# HANC_Analog_TS.net
KiCad netlist of a schematic drawn in Altium Designer
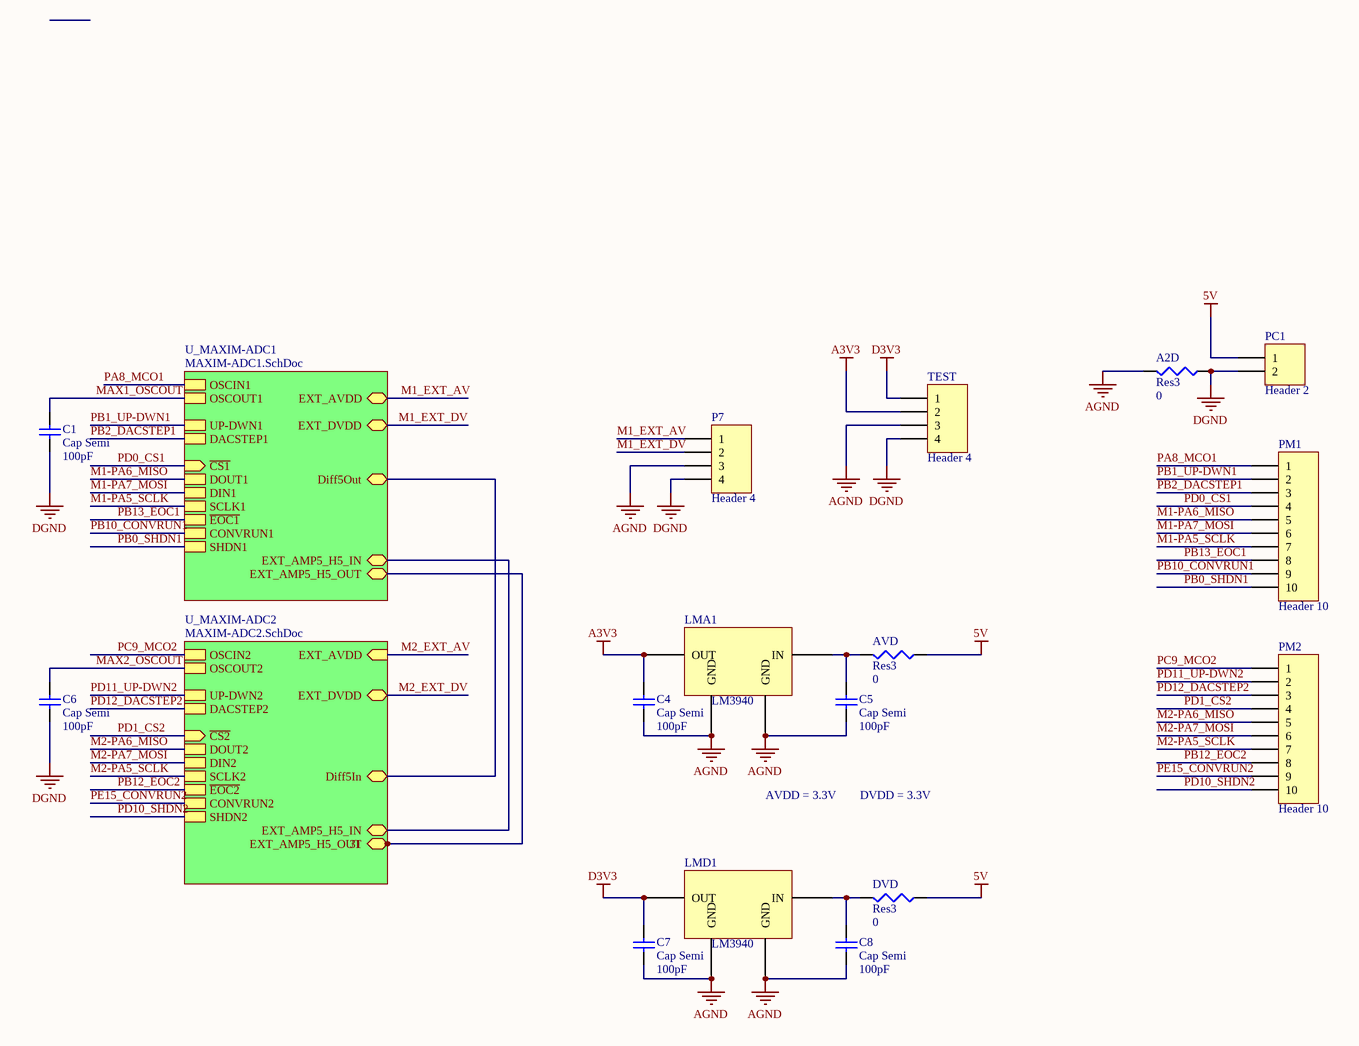
[diagram p0: HANC_Analog_TS.SchDoc]

(export (version "E")
  (design (tool "Eeschema 10.0.6"))
  (components
    (comp (ref "A2D")
      (value "Res3")
      (footprint "J1-0603")
      (description "Resistor")
      (fields (field (name "ALTIUM_VALUE") "0") (field (name "PUBLISHER") "Altium Limited"))
      (libsource (lib "Miscellaneous Devices") (part "Res3"))
    )
    (comp (ref "AVD")
      (value "Res3")
      (footprint "J1-0603")
      (description "Resistor")
      (fields (field (name "ALTIUM_VALUE") "0") (field (name "PUBLISHER") "Altium Limited"))
      (libsource (lib "Miscellaneous Devices") (part "Res3"))
    )
    (comp (ref "C1")
      (value "Cap Semi")
      (footprint "1608[0603]")
      (description "Capacitor (Semiconductor SIM Model)")
      (fields (field (name "ALTIUM_VALUE") "100pF") (field (name "PUBLISHER") "Altium Limited"))
      (libsource (lib "Miscellaneous Devices") (part "Cap Semi"))
    )
    (comp (ref "C4")
      (value "Cap Semi")
      (footprint "1608[0603]")
      (description "Capacitor (Semiconductor SIM Model)")
      (fields (field (name "ALTIUM_VALUE") "100pF") (field (name "PUBLISHER") "Altium Limited"))
      (libsource (lib "Miscellaneous Devices") (part "Cap Semi"))
    )
    (comp (ref "C5")
      (value "Cap Semi")
      (footprint "1608[0603]")
      (description "Capacitor (Semiconductor SIM Model)")
      (fields (field (name "ALTIUM_VALUE") "100pF") (field (name "PUBLISHER") "Altium Limited"))
      (libsource (lib "Miscellaneous Devices") (part "Cap Semi"))
    )
    (comp (ref "C6")
      (value "Cap Semi")
      (footprint "1608[0603]")
      (description "Capacitor (Semiconductor SIM Model)")
      (fields (field (name "ALTIUM_VALUE") "100pF") (field (name "PUBLISHER") "Altium Limited"))
      (libsource (lib "Miscellaneous Devices") (part "Cap Semi"))
    )
    (comp (ref "C7")
      (value "Cap Semi")
      (footprint "1608[0603]")
      (description "Capacitor (Semiconductor SIM Model)")
      (fields (field (name "ALTIUM_VALUE") "100pF") (field (name "PUBLISHER") "Altium Limited"))
      (libsource (lib "Miscellaneous Devices") (part "Cap Semi"))
    )
    (comp (ref "C8")
      (value "Cap Semi")
      (footprint "1608[0603]")
      (description "Capacitor (Semiconductor SIM Model)")
      (fields (field (name "ALTIUM_VALUE") "100pF") (field (name "PUBLISHER") "Altium Limited"))
      (libsource (lib "Miscellaneous Devices") (part "Cap Semi"))
    )
    (comp (ref "DVD")
      (value "Res3")
      (footprint "J1-0603")
      (description "Resistor")
      (fields (field (name "ALTIUM_VALUE") "0") (field (name "PUBLISHER") "Altium Limited"))
      (libsource (lib "Miscellaneous Devices") (part "Res3"))
    )
    (comp (ref "LMA1")
      (value "LM3940")
      (footprint "SOT223_N")
      (libsource (lib "LN3940") (part "Component_1"))
    )
    (comp (ref "LMD1")
      (value "LM3940")
      (footprint "SOT223_N")
      (libsource (lib "LN3940") (part "Component_1"))
    )
    (comp (ref "P7")
      (value "Header 4")
      (footprint "HDR1X4")
      (description "External power for ADC1")
      (fields (field (name "PUBLISHER") "Altium Limited"))
      (libsource (lib "Miscellaneous Connectors") (part "Header 4"))
    )
    (comp (ref "PC1")
      (value "Header 2")
      (footprint "HDR1X2")
      (description "Power for analog board")
      (fields (field (name "PUBLISHER") "Altium Limited"))
      (libsource (lib "Miscellaneous Connectors") (part "Header 2"))
    )
    (comp (ref "PM1")
      (value "Header 10")
      (footprint "HDR1X10")
      (description "GPIO for ADC1")
      (fields (field (name "PUBLISHER") "Altium Limited"))
      (libsource (lib "Miscellaneous Connectors") (part "Header 10"))
    )
    (comp (ref "PM2")
      (value "Header 10")
      (footprint "HDR1X10")
      (description "GPIO for ADC2")
      (fields (field (name "PUBLISHER") "Altium Limited"))
      (libsource (lib "Miscellaneous Connectors") (part "Header 10"))
    )
    (comp (ref "TEST")
      (value "Header 4")
      (footprint "HDR1X4")
      (description "Header, 4-Pin")
      (fields (field (name "PUBLISHER") "Altium Limited"))
      (libsource (lib "Miscellaneous Connectors") (part "Header 4"))
    )
  )
  (nets
    (net (code "4") (name "/M1-PA5_SCLK") (class "Default")
      (node (ref "PM1") (pin "7") (pinfunction "7_7") (pintype "passive"))
    )
    (net (code "5") (name "/M1-PA6_MISO") (class "Default")
      (node (ref "PM1") (pin "5") (pinfunction "5_5") (pintype "passive"))
    )
    (net (code "6") (name "/M1-PA7_MOSI") (class "Default")
      (node (ref "PM1") (pin "6") (pinfunction "6_6") (pintype "passive"))
    )
    (net (code "7") (name "/M1_EXT_AV") (class "Default")
      (node (ref "P7") (pin "1") (pinfunction "1_1") (pintype "passive"))
    )
    (net (code "8") (name "/M1_EXT_DV") (class "Default")
      (node (ref "P7") (pin "2") (pinfunction "2_2") (pintype "passive"))
    )
    (net (code "9") (name "/M2-PA5_SCLK") (class "Default")
      (node (ref "PM2") (pin "7") (pinfunction "7_7") (pintype "passive"))
    )
    (net (code "10") (name "/M2-PA6_MISO") (class "Default")
      (node (ref "PM2") (pin "5") (pinfunction "5_5") (pintype "passive"))
    )
    (net (code "11") (name "/M2-PA7_MOSI") (class "Default")
      (node (ref "PM2") (pin "6") (pinfunction "6_6") (pintype "passive"))
    )
    (net (code "14") (name "/MAX1_OSCOUT") (class "Default")
      (node (ref "C1") (pin "2") (pinfunction "2_2") (pintype "passive"))
    )
    (net (code "15") (name "/MAX2_OSCOUT") (class "Default")
      (node (ref "C6") (pin "2") (pinfunction "2_2") (pintype "passive"))
    )
    (net (code "16") (name "/PA8_MCO1") (class "Default")
      (node (ref "PM1") (pin "1") (pinfunction "1_1") (pintype "passive"))
    )
    (net (code "17") (name "/PB0_SHDN1") (class "Default")
      (node (ref "PM1") (pin "10") (pinfunction "10_10") (pintype "passive"))
    )
    (net (code "18") (name "/PB1_UP-DWN1") (class "Default")
      (node (ref "PM1") (pin "2") (pinfunction "2_2") (pintype "passive"))
    )
    (net (code "19") (name "/PB2_DACSTEP1") (class "Default")
      (node (ref "PM1") (pin "3") (pinfunction "3_3") (pintype "passive"))
    )
    (net (code "20") (name "/PB10_CONVRUN1") (class "Default")
      (node (ref "PM1") (pin "9") (pinfunction "9_9") (pintype "passive"))
    )
    (net (code "21") (name "/PB12_EOC2") (class "Default")
      (node (ref "PM2") (pin "8") (pinfunction "8_8") (pintype "passive"))
    )
    (net (code "22") (name "/PB13_EOC1") (class "Default")
      (node (ref "PM1") (pin "8") (pinfunction "8_8") (pintype "passive"))
    )
    (net (code "23") (name "/PC9_MCO2") (class "Default")
      (node (ref "PM2") (pin "1") (pinfunction "1_1") (pintype "passive"))
    )
    (net (code "24") (name "/PD0_CS1") (class "Default")
      (node (ref "PM1") (pin "4") (pinfunction "4_4") (pintype "passive"))
    )
    (net (code "25") (name "/PD1_CS2") (class "Default")
      (node (ref "PM2") (pin "4") (pinfunction "4_4") (pintype "passive"))
    )
    (net (code "26") (name "/PD10_SHDN2") (class "Default")
      (node (ref "PM2") (pin "10") (pinfunction "10_10") (pintype "passive"))
    )
    (net (code "27") (name "/PD11_UP-DWN2") (class "Default")
      (node (ref "PM2") (pin "2") (pinfunction "2_2") (pintype "passive"))
    )
    (net (code "28") (name "/PD12_DACSTEP2") (class "Default")
      (node (ref "PM2") (pin "3") (pinfunction "3_3") (pintype "passive"))
    )
    (net (code "29") (name "/PE15_CONVRUN2") (class "Default")
      (node (ref "PM2") (pin "9") (pinfunction "9_9") (pintype "passive"))
    )
    (net (code "30") (name "5V") (class "Default")
      (node (ref "AVD") (pin "1") (pinfunction "1_1") (pintype "passive"))
      (node (ref "DVD") (pin "1") (pinfunction "1_1") (pintype "passive"))
      (node (ref "PC1") (pin "1") (pinfunction "1_1") (pintype "passive"))
    )
    (net (code "31") (name "A3V3") (class "Default")
      (node (ref "C4") (pin "2") (pinfunction "2_2") (pintype "passive"))
      (node (ref "LMA1") (pin "3") (pinfunction "OUT_3") (pintype "passive"))
      (node (ref "TEST") (pin "2") (pinfunction "2_2") (pintype "passive"))
    )
    (net (code "32") (name "AGND") (class "Default")
      (node (ref "A2D") (pin "2") (pinfunction "2_2") (pintype "passive"))
      (node (ref "C4") (pin "1") (pinfunction "1_1") (pintype "passive"))
      (node (ref "C5") (pin "1") (pinfunction "1_1") (pintype "passive"))
      (node (ref "C7") (pin "1") (pinfunction "1_1") (pintype "passive"))
      (node (ref "C8") (pin "1") (pinfunction "1_1") (pintype "passive"))
      (node (ref "LMA1") (pin "2") (pinfunction "GND_2") (pintype "passive"))
      (node (ref "LMA1") (pin "4") (pinfunction "GND_4") (pintype "passive"))
      (node (ref "LMD1") (pin "2") (pinfunction "GND_2") (pintype "passive"))
      (node (ref "LMD1") (pin "4") (pinfunction "GND_4") (pintype "passive"))
      (node (ref "P7") (pin "3") (pinfunction "3_3") (pintype "passive"))
      (node (ref "TEST") (pin "3") (pinfunction "3_3") (pintype "passive"))
    )
    (net (code "33") (name "D3V3") (class "Default")
      (node (ref "C7") (pin "2") (pinfunction "2_2") (pintype "passive"))
      (node (ref "LMD1") (pin "3") (pinfunction "OUT_3") (pintype "passive"))
      (node (ref "TEST") (pin "1") (pinfunction "1_1") (pintype "passive"))
    )
    (net (code "34") (name "DGND") (class "Default")
      (node (ref "A2D") (pin "1") (pinfunction "1_1") (pintype "passive"))
      (node (ref "C1") (pin "1") (pinfunction "1_1") (pintype "passive"))
      (node (ref "C6") (pin "1") (pinfunction "1_1") (pintype "passive"))
      (node (ref "P7") (pin "4") (pinfunction "4_4") (pintype "passive"))
      (node (ref "PC1") (pin "2") (pinfunction "2_2") (pintype "passive"))
      (node (ref "TEST") (pin "4") (pinfunction "4_4") (pintype "passive"))
    )
    (net (code "35") (name "Net-(LMA1-IN)") (class "Default")
      (node (ref "AVD") (pin "2") (pinfunction "2_2") (pintype "passive"))
      (node (ref "C5") (pin "2") (pinfunction "2_2") (pintype "passive"))
      (node (ref "LMA1") (pin "1") (pinfunction "IN_1") (pintype "passive"))
    )
    (net (code "36") (name "Net-(LMD1-IN)") (class "Default")
      (node (ref "C8") (pin "2") (pinfunction "2_2") (pintype "passive"))
      (node (ref "DVD") (pin "2") (pinfunction "2_2") (pintype "passive"))
      (node (ref "LMD1") (pin "1") (pinfunction "IN_1") (pintype "passive"))
    )
  )
)
